# DD2090_4CAM_FFC_IMU.net
KiCad netlist of a schematic drawn in Altium Designer
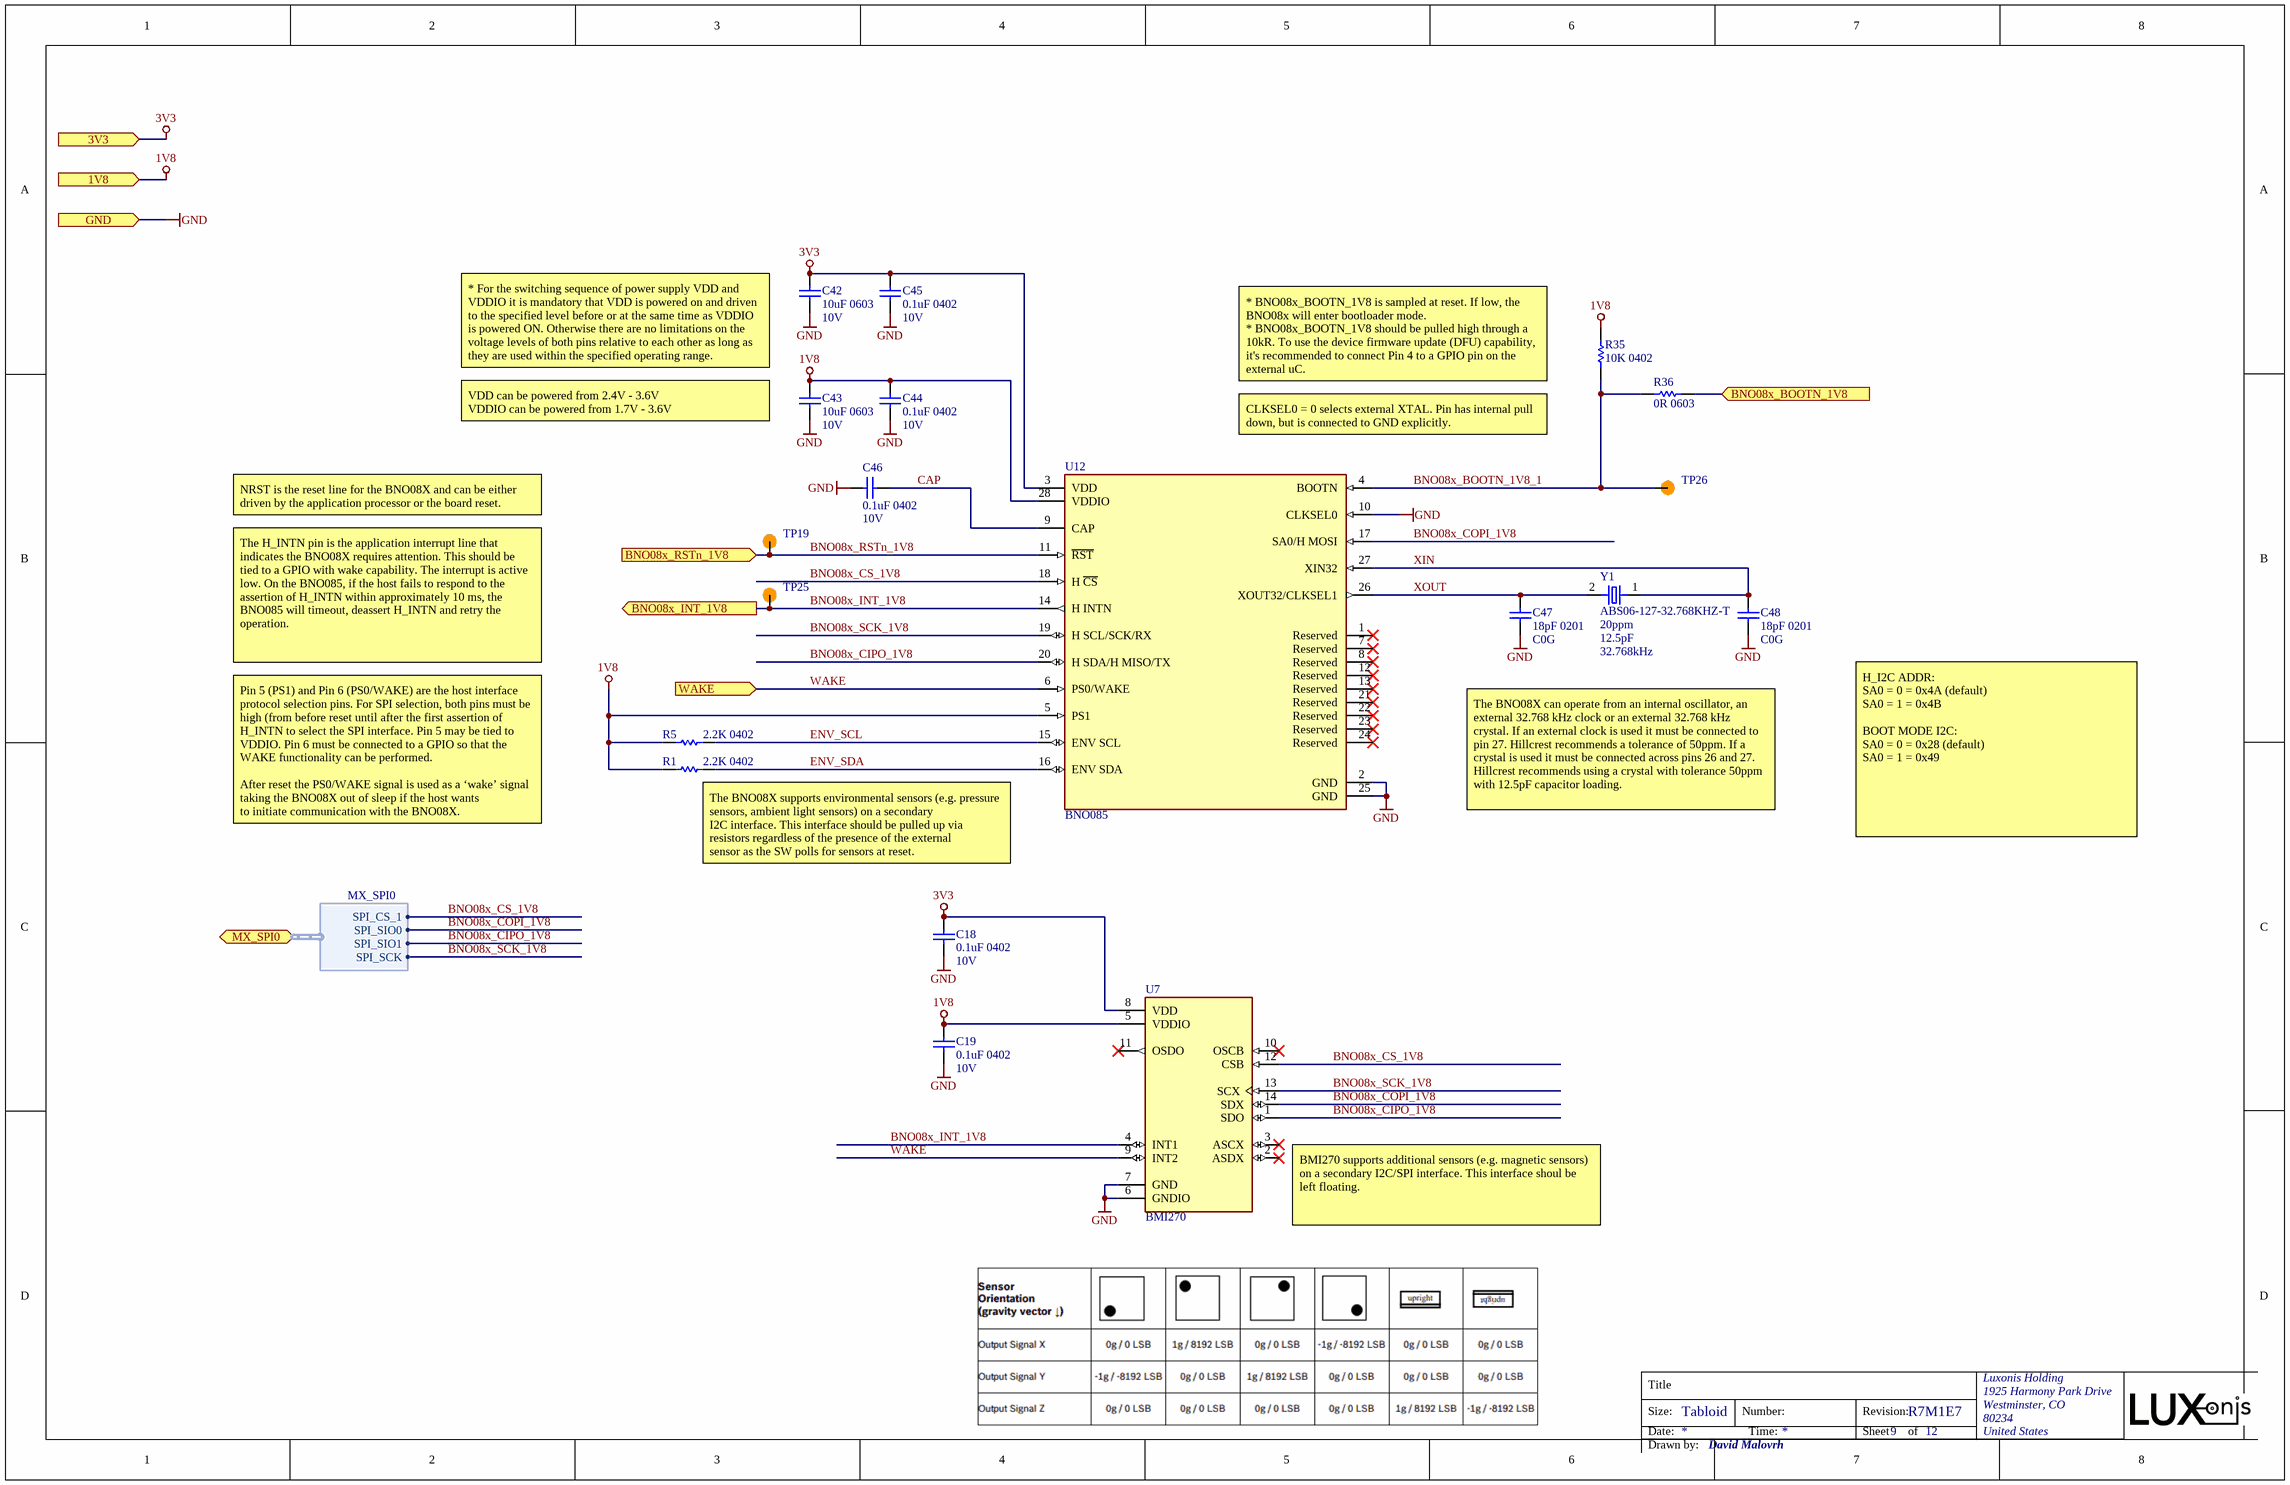
[diagram p0: DD2090_4CAM_FFC_IMU.SchDoc]

(export (version "E")
  (design (tool "Eeschema 10.0.6"))
  (components
    (comp (ref "C18")
      (value "0.1uF 0402")
      (footprint "CAP_Altium_Vault_Generic:CAPC0402(1005)70_L")
      (description "CAP CER 0.1UF 10V X7R 0402 5%")
      (fields (field (name "TOLERANCE") "5%") (field (name "VOLTAGE RATING") "10V"))
      (libsource (lib "LuxonisMaster") (part "GRM155R71A104JA01D"))
    )
    (comp (ref "C19")
      (value "0.1uF 0402")
      (footprint "CAP_Altium_Vault_Generic:CAPC0402(1005)70_L")
      (description "CAP CER 0.1UF 10V X7R 0402 5%")
      (fields (field (name "TOLERANCE") "5%") (field (name "VOLTAGE RATING") "10V"))
      (libsource (lib "LuxonisMaster") (part "GRM155R71A104JA01D"))
    )
    (comp (ref "C42")
      (value "10uF 0603")
      (footprint "CAP_Altium_Vault_Generic:CAPC0603(1608)100_L")
      (description "CAP CER 10UF 10V X5R 0603 20%")
      (fields (field (name "TOLERANCE") "20%") (field (name "VOLTAGE RATING") "10V"))
      (libsource (lib "LuxonisMaster") (part "GRM188R61A106ME69D"))
    )
    (comp (ref "C43")
      (value "10uF 0603")
      (footprint "CAP_Altium_Vault_Generic:CAPC0603(1608)100_L")
      (description "CAP CER 10UF 10V X5R 0603 20%")
      (fields (field (name "TOLERANCE") "20%") (field (name "VOLTAGE RATING") "10V"))
      (libsource (lib "LuxonisMaster") (part "GRM188R61A106ME69D"))
    )
    (comp (ref "C44")
      (value "0.1uF 0402")
      (footprint "CAP_Altium_Vault_Generic:CAPC0402(1005)70_L")
      (description "CAP CER 0.1UF 10V X7R 0402 5%")
      (fields (field (name "TOLERANCE") "5%") (field (name "VOLTAGE RATING") "10V"))
      (libsource (lib "LuxonisMaster") (part "GRM155R71A104JA01D"))
    )
    (comp (ref "C45")
      (value "0.1uF 0402")
      (footprint "CAP_Altium_Vault_Generic:CAPC0402(1005)70_L")
      (description "CAP CER 0.1UF 10V X7R 0402 5%")
      (fields (field (name "TOLERANCE") "5%") (field (name "VOLTAGE RATING") "10V"))
      (libsource (lib "LuxonisMaster") (part "GRM155R71A104JA01D"))
    )
    (comp (ref "C46")
      (value "0.1uF 0402")
      (footprint "CAP_Altium_Vault_Generic:CAPC0402(1005)70_L")
      (description "CAP CER 0.1UF 10V X7R 0402 5%")
      (fields (field (name "TOLERANCE") "5%") (field (name "VOLTAGE RATING") "10V"))
      (libsource (lib "LuxonisMaster") (part "GRM155R71A104JA01D"))
    )
    (comp (ref "C47")
      (value "18pF 0201")
      (footprint "CAP_Altium_Vault_Generic:CAPC0201(0603)33_L")
      (description "Cap Ceramic 18pF 25V C0G 1% Pad SMD 0201 125C T/R")
      (fields (field (name "TOLERANCE") "1%") (field (name "DIELECTRIC") "C0G"))
      (libsource (lib "BW1092_R0M0E0") (part "GRM0335C1E180FA01D"))
    )
    (comp (ref "C48")
      (value "18pF 0201")
      (footprint "CAP_Altium_Vault_Generic:CAPC0201(0603)33_L")
      (description "Cap Ceramic 18pF 25V C0G 1% Pad SMD 0201 125C T/R")
      (fields (field (name "TOLERANCE") "1%") (field (name "DIELECTRIC") "C0G"))
      (libsource (lib "BW1092_R0M0E0") (part "GRM0335C1E180FA01D"))
    )
    (comp (ref "R1")
      (value "2.2K 0402")
      (footprint "RES_Altium_Vault_Generic:RESC0402(1005)_L")
      (description "RES SMD 2.2K OHM 1% 1/16W 0402")
      (fields (field (name "TOLERANCE") "1%"))
      (libsource (lib "LuxonisMaster") (part "RC0402FR-072K2L"))
    )
    (comp (ref "R5")
      (value "2.2K 0402")
      (footprint "RES_Altium_Vault_Generic:RESC0402(1005)_L")
      (description "RES SMD 2.2K OHM 1% 1/16W 0402")
      (fields (field (name "TOLERANCE") "1%"))
      (libsource (lib "LuxonisMaster") (part "RC0402FR-072K2L"))
    )
    (comp (ref "R35")
      (value "10K 0402")
      (footprint "RES_Altium_Vault_Generic:RESC0402(1005)_L")
      (fields (field (name "TOLERANCE") "1%"))
      (libsource (lib "LuxonisMaster") (part "RC0402FR-1310KL"))
    )
    (comp (ref "R36")
      (value "0R 0603")
      (footprint "RES_Altium_Vault_Generic:RESC0603(1608)_L")
      (fields (field (name "TOLERANCE") "5%"))
      (libsource (lib "LuxonisMaster") (part "CRCW06030000Z0EA"))
    )
    (comp (ref "TP19")
      (value "TP100_200_NS")
      (footprint "LuxonisMaster:TP100_200_NS")
      (libsource (lib "LuxonisMaster") (part "TEST_POINT"))
    )
    (comp (ref "TP25")
      (value "TP100_200_NS")
      (footprint "LuxonisMaster:TP100_200_NS")
      (libsource (lib "LuxonisMaster") (part "TEST_POINT"))
    )
    (comp (ref "TP26")
      (value "TP100_200_NS")
      (footprint "LuxonisMaster:TP100_200_NS")
      (libsource (lib "LuxonisMaster") (part "TEST_POINT"))
    )
    (comp (ref "U7")
      (value "BMI270")
      (footprint "XDCR_BMI270")
      (description "Accelerometer, Gyroscope, 6 Axis Sensor IÂ²C, SPI Output")
      (libsource (lib "DM1098LUXD-LITE") (part "BMI270"))
    )
    (comp (ref "U12")
      (value "BNO085")
      (footprint "BNO085")
      (description "IMU ACCEL/GYRO/MAG I2C 32BIT")
      (libsource (lib "DM1092_R0M0E0") (part "BNO085"))
    )
    (comp (ref "Y1")
      (value "ABS06-127-32.768KHZ-T")
      (footprint "ABS06-127-32.768KHZ-T")
      (description "CRYSTAL 32.768kHz ±20ppm Crystal 12.5pF 90 kOhms 2-SMD, No Lead")
      (fields
        (field (name "FREQUENCY TOLERANCE") "20ppm")
        (field (name "LOAD CAPACITANCE") "12.5pF")
        (field (name "FREQUENCY") "32.768kHz")
      )
      (libsource (lib "DM1092_R0M0E0") (part "ABS06-127-32.768KHZ-T"))
    )
  )
  (nets
    (net (code "2") (name "/BNO08x_BOOTN_1V8") (class "Default")
      (node (ref "R36") (pin "2") (pinfunction "2_2") (pintype "passive"))
    )
    (net (code "3") (name "/BNO08x_BOOTN_1V8_1") (class "Default")
      (node (ref "R35") (pin "1") (pinfunction "1_1") (pintype "passive"))
      (node (ref "R36") (pin "1") (pinfunction "1_1") (pintype "passive"))
      (node (ref "TP26") (pin "1") (pintype "passive"))
      (node (ref "U12") (pin "4") (pinfunction "BOOTN_4") (pintype "input"))
    )
    (net (code "4") (name "/BNO08x_CIPO_1V8") (class "Default")
      (node (ref "U12") (pin "20") (pinfunction "H_SDA/H_MISO/TX_20") (pintype "bidirectional"))
      (node (ref "U7") (pin "1") (pinfunction "SDO_1") (pintype "bidirectional"))
    )
    (net (code "5") (name "/BNO08x_COPI_1V8") (class "Default")
      (node (ref "U12") (pin "17") (pinfunction "SA0/H_MOSI_17") (pintype "input"))
      (node (ref "U7") (pin "14") (pinfunction "SDX_14") (pintype "bidirectional"))
    )
    (net (code "6") (name "/BNO08x_CS_1V8") (class "Default")
      (node (ref "U12") (pin "18") (pinfunction "H_~{CS}_18") (pintype "input"))
      (node (ref "U7") (pin "12") (pinfunction "CSB_12") (pintype "input"))
    )
    (net (code "7") (name "/BNO08x_INT_1V8") (class "Default")
      (node (ref "TP25") (pin "1") (pintype "passive"))
      (node (ref "U12") (pin "14") (pinfunction "H_INTN_14") (pintype "output"))
      (node (ref "U7") (pin "4") (pinfunction "INT1_4") (pintype "bidirectional"))
    )
    (net (code "8") (name "/BNO08x_RSTn_1V8") (class "Default")
      (node (ref "TP19") (pin "1") (pintype "passive"))
      (node (ref "U12") (pin "11") (pinfunction "~{RST}_11") (pintype "input"))
    )
    (net (code "9") (name "/BNO08x_SCK_1V8") (class "Default")
      (node (ref "U12") (pin "19") (pinfunction "H_SCL/SCK/RX_19") (pintype "bidirectional"))
      (node (ref "U7") (pin "13") (pinfunction "SCX_13") (pintype "input"))
    )
    (net (code "10") (name "/CAP") (class "Default")
      (node (ref "C46") (pin "1") (pinfunction "1_1") (pintype "passive"))
      (node (ref "U12") (pin "9") (pinfunction "CAP_9") (pintype "passive"))
    )
    (net (code "11") (name "/ENV_SCL") (class "Default")
      (node (ref "R5") (pin "2") (pinfunction "2_2") (pintype "passive"))
      (node (ref "U12") (pin "15") (pinfunction "ENV_SCL_15") (pintype "bidirectional"))
    )
    (net (code "12") (name "/ENV_SDA") (class "Default")
      (node (ref "R1") (pin "2") (pinfunction "2_2") (pintype "passive"))
      (node (ref "U12") (pin "16") (pinfunction "ENV_SDA_16") (pintype "bidirectional"))
    )
    (net (code "13") (name "/WAKE") (class "Default")
      (node (ref "U12") (pin "6") (pinfunction "PS0/WAKE_6") (pintype "input"))
      (node (ref "U7") (pin "9") (pinfunction "INT2_9") (pintype "bidirectional"))
    )
    (net (code "14") (name "/XIN") (class "Default")
      (node (ref "C48") (pin "2") (pinfunction "2_2") (pintype "passive"))
      (node (ref "U12") (pin "27") (pinfunction "XIN32_27") (pintype "input"))
      (node (ref "Y1") (pin "1") (pinfunction "1_1") (pintype "passive"))
    )
    (net (code "15") (name "/XOUT") (class "Default")
      (node (ref "C47") (pin "2") (pinfunction "2_2") (pintype "passive"))
      (node (ref "U12") (pin "26") (pinfunction "XOUT32/CLKSEL1_26") (pintype "output"))
      (node (ref "Y1") (pin "2") (pinfunction "2_2") (pintype "passive"))
    )
    (net (code "17") (name "1V8") (class "Default")
      (node (ref "C19") (pin "2") (pinfunction "2_2") (pintype "passive"))
      (node (ref "C43") (pin "2") (pinfunction "2_2") (pintype "passive"))
      (node (ref "C44") (pin "2") (pinfunction "2_2") (pintype "passive"))
      (node (ref "R1") (pin "1") (pinfunction "1_1") (pintype "passive"))
      (node (ref "R35") (pin "2") (pinfunction "2_2") (pintype "passive"))
      (node (ref "R5") (pin "1") (pinfunction "1_1") (pintype "passive"))
      (node (ref "U12") (pin "28") (pinfunction "VDDIO_28") (pintype "power_in"))
      (node (ref "U12") (pin "5") (pinfunction "PS1_5") (pintype "input"))
      (node (ref "U7") (pin "5") (pinfunction "VDDIO_5") (pintype "power_in"))
    )
    (net (code "18") (name "3V3") (class "Default")
      (node (ref "C18") (pin "2") (pinfunction "2_2") (pintype "passive"))
      (node (ref "C42") (pin "2") (pinfunction "2_2") (pintype "passive"))
      (node (ref "C45") (pin "2") (pinfunction "2_2") (pintype "passive"))
      (node (ref "U12") (pin "3") (pinfunction "VDD_3") (pintype "power_in"))
      (node (ref "U7") (pin "8") (pinfunction "VDD_8") (pintype "power_in"))
    )
    (net (code "19") (name "GND") (class "Default")
      (node (ref "C18") (pin "1") (pinfunction "1_1") (pintype "passive"))
      (node (ref "C19") (pin "1") (pinfunction "1_1") (pintype "passive"))
      (node (ref "C42") (pin "1") (pinfunction "1_1") (pintype "passive"))
      (node (ref "C43") (pin "1") (pinfunction "1_1") (pintype "passive"))
      (node (ref "C44") (pin "1") (pinfunction "1_1") (pintype "passive"))
      (node (ref "C45") (pin "1") (pinfunction "1_1") (pintype "passive"))
      (node (ref "C46") (pin "2") (pinfunction "2_2") (pintype "passive"))
      (node (ref "C47") (pin "1") (pinfunction "1_1") (pintype "passive"))
      (node (ref "C48") (pin "1") (pinfunction "1_1") (pintype "passive"))
      (node (ref "U12") (pin "10") (pinfunction "CLKSEL0_10") (pintype "input"))
      (node (ref "U12") (pin "2") (pinfunction "GND_2") (pintype "power_in"))
      (node (ref "U12") (pin "25") (pinfunction "GND_25") (pintype "power_in"))
      (node (ref "U7") (pin "6") (pinfunction "GNDIO_6") (pintype "power_in"))
      (node (ref "U7") (pin "7") (pinfunction "GND_7") (pintype "power_in"))
    )
    (net (code "20") (name "unconnected-(U7-ASCX-Pad3)") (class "Default")
      (node (ref "U7") (pin "3") (pinfunction "ASCX_3") (pintype "bidirectional+no_connect"))
    )
    (net (code "21") (name "unconnected-(U7-ASDX-Pad2)") (class "Default")
      (node (ref "U7") (pin "2") (pinfunction "ASDX_2") (pintype "bidirectional+no_connect"))
    )
    (net (code "22") (name "unconnected-(U7-OSCB-Pad10)") (class "Default")
      (node (ref "U7") (pin "10") (pinfunction "OSCB_10") (pintype "input+no_connect"))
    )
    (net (code "23") (name "unconnected-(U7-OSDO-Pad11)") (class "Default")
      (node (ref "U7") (pin "11") (pinfunction "OSDO_11") (pintype "output+no_connect"))
    )
    (net (code "24") (name "unconnected-(U12-Reserved-Pad1)") (class "Default")
      (node (ref "U12") (pin "1") (pinfunction "Reserved_1") (pintype "passive+no_connect"))
    )
    (net (code "25") (name "unconnected-(U12-Reserved-Pad7)") (class "Default")
      (node (ref "U12") (pin "7") (pinfunction "Reserved_7") (pintype "passive+no_connect"))
    )
    (net (code "26") (name "unconnected-(U12-Reserved-Pad8)") (class "Default")
      (node (ref "U12") (pin "8") (pinfunction "Reserved_8") (pintype "passive+no_connect"))
    )
    (net (code "27") (name "unconnected-(U12-Reserved-Pad12)") (class "Default")
      (node (ref "U12") (pin "12") (pinfunction "Reserved_12") (pintype "passive+no_connect"))
    )
    (net (code "28") (name "unconnected-(U12-Reserved-Pad13)") (class "Default")
      (node (ref "U12") (pin "13") (pinfunction "Reserved_13") (pintype "passive+no_connect"))
    )
    (net (code "29") (name "unconnected-(U12-Reserved-Pad21)") (class "Default")
      (node (ref "U12") (pin "21") (pinfunction "Reserved_21") (pintype "passive+no_connect"))
    )
    (net (code "30") (name "unconnected-(U12-Reserved-Pad22)") (class "Default")
      (node (ref "U12") (pin "22") (pinfunction "Reserved_22") (pintype "passive+no_connect"))
    )
    (net (code "31") (name "unconnected-(U12-Reserved-Pad23)") (class "Default")
      (node (ref "U12") (pin "23") (pinfunction "Reserved_23") (pintype "passive+no_connect"))
    )
    (net (code "32") (name "unconnected-(U12-Reserved-Pad24)") (class "Default")
      (node (ref "U12") (pin "24") (pinfunction "Reserved_24") (pintype "passive+no_connect"))
    )
  )
)
